# POWER.net
KiCad netlist of a schematic drawn in Altium Designer
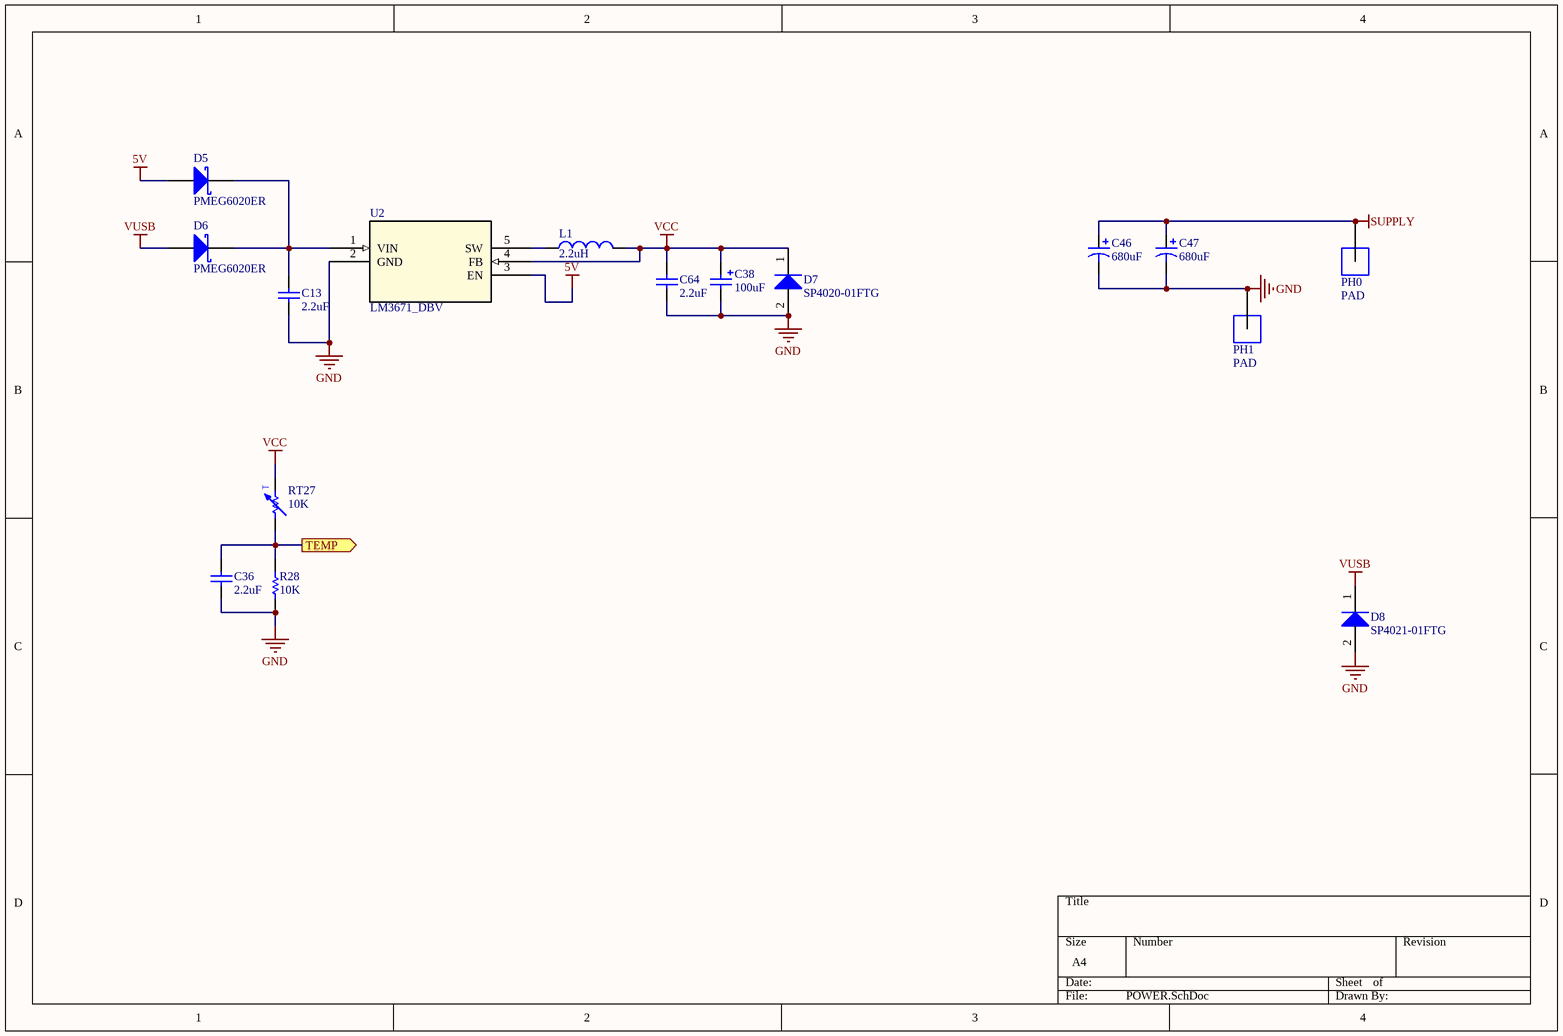
[diagram p0: POWER.SchDoc]

(export (version "E")
  (design (tool "Eeschema 10.0.6"))
  (components
    (comp (ref "C13")
      (value "2.2uF")
      (footprint "C1206[3216X160]")
      (description "2.2uF 6.3V 10% 1206 (3216 Metric)")
      (fields (field (name "PARTNUMBER") "GRM31CR60J476KE19L") (field (name "MANUFACTURER") "Murata"))
      (libsource (lib "Capacitors") (part "CAP_2.2uF_16V_1206_10%"))
    )
    (comp (ref "C36")
      (value "2.2uF")
      (footprint "C0603[1608X92]")
      (description "2.2uF 6.3V 10% 0603 (1608 Metric)")
      (fields (field (name "PARTNUMBER") "GRM185R60J225KE26D") (field (name "MANUFACTURER") "Murata"))
      (libsource (lib "Capacitors") (part "CAP_2.2uF_6.3V_0603_10%"))
    )
    (comp (ref "C38")
      (value "100uF")
      (footprint "C1206[3216X105]_Tantal")
      (description "TANTAL 100uF 16V 20% 1206 (3216 Metric)")
      (fields (field (name "PARTNUMBER") "F931C107MCCAJ6") (field (name "MANUFACTURER") "AVX Corporation"))
      (libsource (lib "Capacitors") (part "CAP_100uF_16V_1206_20%"))
    )
    (comp (ref "C46")
      (value "680uF")
      (footprint "CAP_ELEC_THRU_5MM_HORZ")
      (description "680uF 63V 20%  EC")
      (fields
        (field (name "PARTNUMBER") "EKZN630ELL681MK30S")
        (field (name "MANUFACTURER") "United Chemi-Con")
      )
      (libsource (lib "Capacitors") (part "CAP_680uF_63V_20%"))
    )
    (comp (ref "C47")
      (value "680uF")
      (footprint "CAP_ELEC_THRU_5MM_HORZ")
      (description "680uF 63V 20%  EC")
      (fields
        (field (name "PARTNUMBER") "EKZN630ELL681MK30S")
        (field (name "MANUFACTURER") "United Chemi-Con")
      )
      (libsource (lib "Capacitors") (part "CAP_680uF_63V_20%"))
    )
    (comp (ref "C64")
      (value "2.2uF")
      (footprint "C1206[3216X160]")
      (description "2.2uF 6.3V 10% 1206 (3216 Metric)")
      (fields (field (name "PARTNUMBER") "GRM31CR60J476KE19L") (field (name "MANUFACTURER") "Murata"))
      (libsource (lib "Capacitors") (part "CAP_2.2uF_16V_1206_10%"))
    )
    (comp (ref "D5")
      (value "PMEG6020ER")
      (footprint "SOD-123")
      (fields (field (name "PARTNUMBER") "PMEG6020ER,115") (field (name "MANUFACTURER") "NXP Semiconductors"))
      (libsource (lib "Diodes") (part "PMEG6020ER"))
    )
    (comp (ref "D6")
      (value "PMEG6020ER")
      (footprint "SOD-123")
      (fields (field (name "PARTNUMBER") "PMEG6020ER,115") (field (name "MANUFACTURER") "NXP Semiconductors"))
      (libsource (lib "Diodes") (part "PMEG6020ER"))
    )
    (comp (ref "D7")
      (value "SP4020-01FTG")
      (footprint "SOD-323")
      (fields (field (name "MANUFACTURER") "Littelfuse"))
      (libsource (lib "Diodes") (part "SP4020-01FTG"))
    )
    (comp (ref "D8")
      (value "SP4021-01FTG")
      (footprint "SOD-323")
      (fields (field (name "MANUFACTURER") "Littelfuse"))
      (libsource (lib "Diodes-TVS") (part "SP4021-01FTG"))
    )
    (comp (ref "L1")
      (value "2.2uH")
      (footprint "IND0805")
      (description "2.2uH 20% 1.7A 0805")
      (fields (field (name "PARTNUMBER") "LQM21PN2R2MGHL") (field (name "MANUFACTURER") "Murata"))
      (libsource (lib "Inductors") (part "IND_2.2uH_1.7A_0805_20%"))
    )
    (comp (ref "PH0") (value "PAD") (footprint "PAD") (libsource (lib "Component") (part "PAD")))
    (comp (ref "PH1") (value "PAD") (footprint "PAD") (libsource (lib "Component") (part "PAD")))
    (comp (ref "R28")
      (value "10K")
      (footprint "R0603[1608]")
      (description "10K 0.25W 1% 0603 (1005 Metric)")
      (fields (field (name "MANUFACTURER") "Vishay") (field (name "PARTNUMBER") "RCS060310K0FKEA"))
      (libsource (lib "Resistors") (part "RES_10K_0603_1%"))
    )
    (comp (ref "RT27")
      (value "10K")
      (footprint "R0603[1608]")
      (description "NTC 10K 0.5% 0603 (1608 Metric)")
      (fields (field (name "PARTNUMBER") "NCP18XH103D60RC") (field (name "MANUFACTURER") "Murata"))
      (libsource (lib "Resistors") (part "NTC_10K_0603_0.5%"))
    )
    (comp (ref "U2")
      (value "LM3671_DBV")
      (footprint "SOT23/MF05A")
      (description "600-mA Step-Down DC-DC Converter")
      (fields (field (name "MANUFACTURER") "Texas Instruments"))
      (libsource (lib "ICs") (part "LM3671_DBV"))
    )
  )
  (nets
    (net (code "1") (name "/TEMP") (class "Default")
      (node (ref "C36") (pin "2") (pinfunction "2_2") (pintype "passive"))
      (node (ref "R28") (pin "2") (pinfunction "2_2") (pintype "passive"))
      (node (ref "RT27") (pin "1") (pinfunction "1_1") (pintype "passive"))
    )
    (net (code "2") (name "5V") (class "Default")
      (node (ref "D5") (pin "2") (pinfunction "A_2") (pintype "passive"))
      (node (ref "U2") (pin "3") (pinfunction "EN_3") (pintype "passive"))
    )
    (net (code "3") (name "GND") (class "Default")
      (node (ref "C13") (pin "2") (pinfunction "2_2") (pintype "passive"))
      (node (ref "C36") (pin "1") (pinfunction "1_1") (pintype "passive"))
      (node (ref "C38") (pin "2") (pinfunction "2_2") (pintype "passive"))
      (node (ref "C46") (pin "2") (pinfunction "2_2") (pintype "passive"))
      (node (ref "C47") (pin "2") (pinfunction "2_2") (pintype "passive"))
      (node (ref "C64") (pin "2") (pinfunction "2_2") (pintype "passive"))
      (node (ref "D7") (pin "2") (pinfunction "A_2") (pintype "passive"))
      (node (ref "D8") (pin "2") (pinfunction "A_2") (pintype "passive"))
      (node (ref "PH1") (pin "0") (pinfunction "PH_0") (pintype "passive"))
      (node (ref "R28") (pin "1") (pinfunction "1_1") (pintype "passive"))
      (node (ref "U2") (pin "2") (pinfunction "GND_2") (pintype "power_in"))
    )
    (net (code "4") (name "Net-(D5-K)") (class "Default")
      (node (ref "C13") (pin "1") (pinfunction "1_1") (pintype "passive"))
      (node (ref "D5") (pin "1") (pinfunction "K_1") (pintype "passive"))
      (node (ref "D6") (pin "1") (pinfunction "K_1") (pintype "passive"))
      (node (ref "U2") (pin "1") (pinfunction "VIN_1") (pintype "input"))
    )
    (net (code "5") (name "Net-(U2-SW)") (class "Default")
      (node (ref "L1") (pin "1") (pinfunction "1_1") (pintype "passive"))
      (node (ref "U2") (pin "5") (pinfunction "SW_5") (pintype "passive"))
    )
    (net (code "6") (name "SUPPLY") (class "Default")
      (node (ref "C46") (pin "1") (pinfunction "1_1") (pintype "passive"))
      (node (ref "C47") (pin "1") (pinfunction "1_1") (pintype "passive"))
      (node (ref "PH0") (pin "0") (pinfunction "PH_0") (pintype "passive"))
    )
    (net (code "7") (name "VCC") (class "Default")
      (node (ref "C38") (pin "1") (pinfunction "1_1") (pintype "passive"))
      (node (ref "C64") (pin "1") (pinfunction "1_1") (pintype "passive"))
      (node (ref "D7") (pin "1") (pinfunction "K_1") (pintype "passive"))
      (node (ref "L1") (pin "2") (pinfunction "2_2") (pintype "passive"))
      (node (ref "RT27") (pin "2") (pinfunction "2_2") (pintype "passive"))
      (node (ref "U2") (pin "4") (pinfunction "FB_4") (pintype "input"))
    )
    (net (code "8") (name "VUSB") (class "Default")
      (node (ref "D6") (pin "2") (pinfunction "A_2") (pintype "passive"))
      (node (ref "D8") (pin "1") (pinfunction "K_1") (pintype "passive"))
    )
  )
)
